# mic.net
KiCad netlist of a schematic drawn in Altium Designer
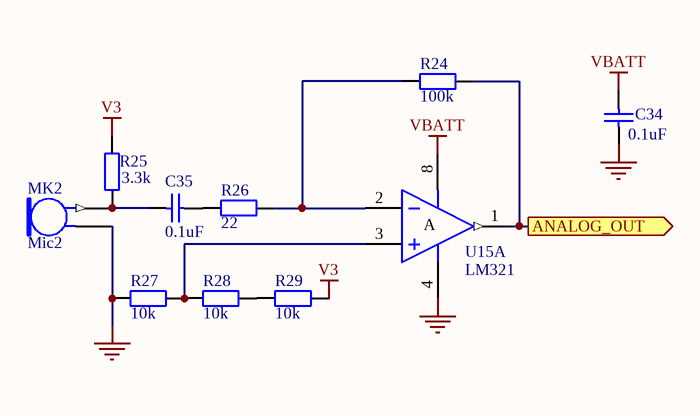
[diagram p0: mic.SchDoc]

(export (version "E")
  (design (tool "Eeschema 10.0.6"))
  (components
    (comp (ref "C34")
      (value "0.1uF")
      (footprint "CAPC2012L")
      (description "Capacitor")
      (fields (field (name "PUBLISHER") "Altium Limited"))
      (libsource (lib "") (part "Cap_1"))
    )
    (comp (ref "C35")
      (value "0.1uF")
      (footprint "CAPC1608L")
      (description "Capacitor")
      (fields (field (name "PUBLISHER") "Altium Limited"))
      (libsource (lib "*") (part "Cap"))
    )
    (comp (ref "MK2")
      (value "Mic2")
      (footprint "electret_6mm")
      (description "Microphone")
      (fields (field (name "PUBLISHER") "*"))
      (libsource (lib "*") (part "Mic2"))
    )
    (comp (ref "R24")
      (value "100k")
      (footprint "RESC1608L")
      (description "Resistor")
      (fields (field (name "PUBLISHER") "Altium Limited"))
      (libsource (lib "") (part "Res2_1"))
    )
    (comp (ref "R25")
      (value "3.3k")
      (footprint "RESC1608L")
      (description "Resistor")
      (fields (field (name "PUBLISHER") "Altium Limited"))
      (libsource (lib "*") (part "Res2"))
    )
    (comp (ref "R26")
      (value "22")
      (footprint "RESC1608L")
      (description "Resistor")
      (fields (field (name "PUBLISHER") "Altium Limited"))
      (libsource (lib "") (part "Res2_1"))
    )
    (comp (ref "R27")
      (value "10k")
      (footprint "RESC1608L")
      (description "Resistor")
      (fields (field (name "PUBLISHER") "Altium Limited"))
      (libsource (lib "") (part "Res2_1"))
    )
    (comp (ref "R28")
      (value "10k")
      (footprint "RESC1608L")
      (description "Resistor")
      (fields (field (name "PUBLISHER") "Altium Limited"))
      (libsource (lib "") (part "Res2_1"))
    )
    (comp (ref "R29")
      (value "10k")
      (footprint "RESC1608L")
      (description "Resistor")
      (fields (field (name "PUBLISHER") "Altium Limited"))
      (libsource (lib "") (part "Res2_1"))
    )
    (comp (ref "U15")
      (value "LM321")
      (description "Dual Operational Amplifier")
      (fields (field (name "PUBLISHER") "Altium Limited"))
      (libsource (lib "TI Operational Amplifier") (part "LM358D"))
    )
  )
  (nets
    (net (code "1") (name "/ANALOG_OUT") (class "Default")
      (node (ref "R24") (pin "2") (pinfunction "2_2") (pintype "passive"))
      (node (ref "U15") (pin "1") (pinfunction "OUT_1") (pintype "output"))
    )
    (net (code "2") (name "GND") (class "Default")
      (node (ref "C34") (pin "2") (pinfunction "2_2") (pintype "passive"))
      (node (ref "MK2") (pin "2") (pinfunction "2_2") (pintype "power_in"))
      (node (ref "R27") (pin "1") (pinfunction "1_1") (pintype "passive"))
      (node (ref "U15") (pin "4") (pinfunction "V-_4") (pintype "power_in"))
    )
    (net (code "3") (name "Net-(C35-Pad1)") (class "Default")
      (node (ref "C35") (pin "1") (pinfunction "1_1") (pintype "passive"))
      (node (ref "R26") (pin "1") (pinfunction "1_1") (pintype "passive"))
    )
    (net (code "4") (name "Net-(C35-Pad2)") (class "Default")
      (node (ref "C35") (pin "2") (pinfunction "2_2") (pintype "passive"))
      (node (ref "MK2") (pin "1") (pinfunction "1_1") (pintype "output"))
      (node (ref "R25") (pin "2") (pinfunction "2_2") (pintype "passive"))
    )
    (net (code "5") (name "Net-(R28-Pad2)") (class "Default")
      (node (ref "R28") (pin "2") (pinfunction "2_2") (pintype "passive"))
      (node (ref "R29") (pin "1") (pinfunction "1_1") (pintype "passive"))
    )
    (net (code "6") (name "Net-(U15A-IN+)") (class "Default")
      (node (ref "R27") (pin "2") (pinfunction "2_2") (pintype "passive"))
      (node (ref "R28") (pin "1") (pinfunction "1_1") (pintype "passive"))
      (node (ref "U15") (pin "3") (pinfunction "IN+_3") (pintype "passive"))
    )
    (net (code "7") (name "Net-(U15A-IN-)") (class "Default")
      (node (ref "R24") (pin "1") (pinfunction "1_1") (pintype "passive"))
      (node (ref "R26") (pin "2") (pinfunction "2_2") (pintype "passive"))
      (node (ref "U15") (pin "2") (pinfunction "IN-_2") (pintype "passive"))
    )
    (net (code "8") (name "V3") (class "Default")
      (node (ref "R25") (pin "1") (pinfunction "1_1") (pintype "passive"))
      (node (ref "R29") (pin "2") (pinfunction "2_2") (pintype "passive"))
    )
    (net (code "9") (name "VBATT") (class "Default")
      (node (ref "C34") (pin "1") (pinfunction "1_1") (pintype "passive"))
      (node (ref "U15") (pin "8") (pinfunction "V+_8") (pintype "power_in"))
    )
  )
)
